# Wiring.net
KiCad netlist of a schematic drawn in EAGLE
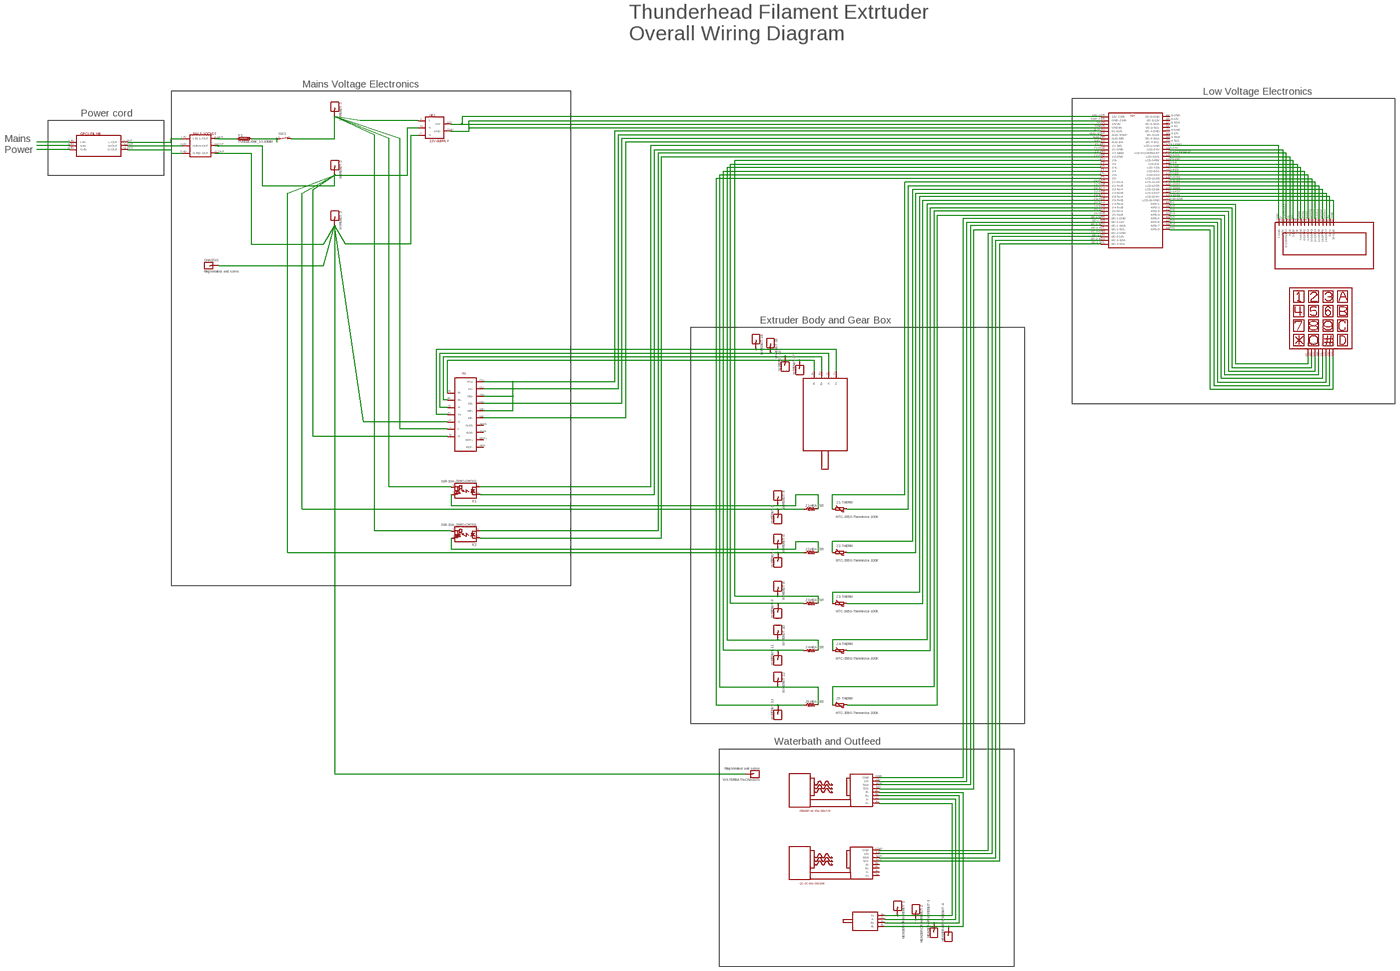
[diagram p0: schematic, sheet 1, overview]
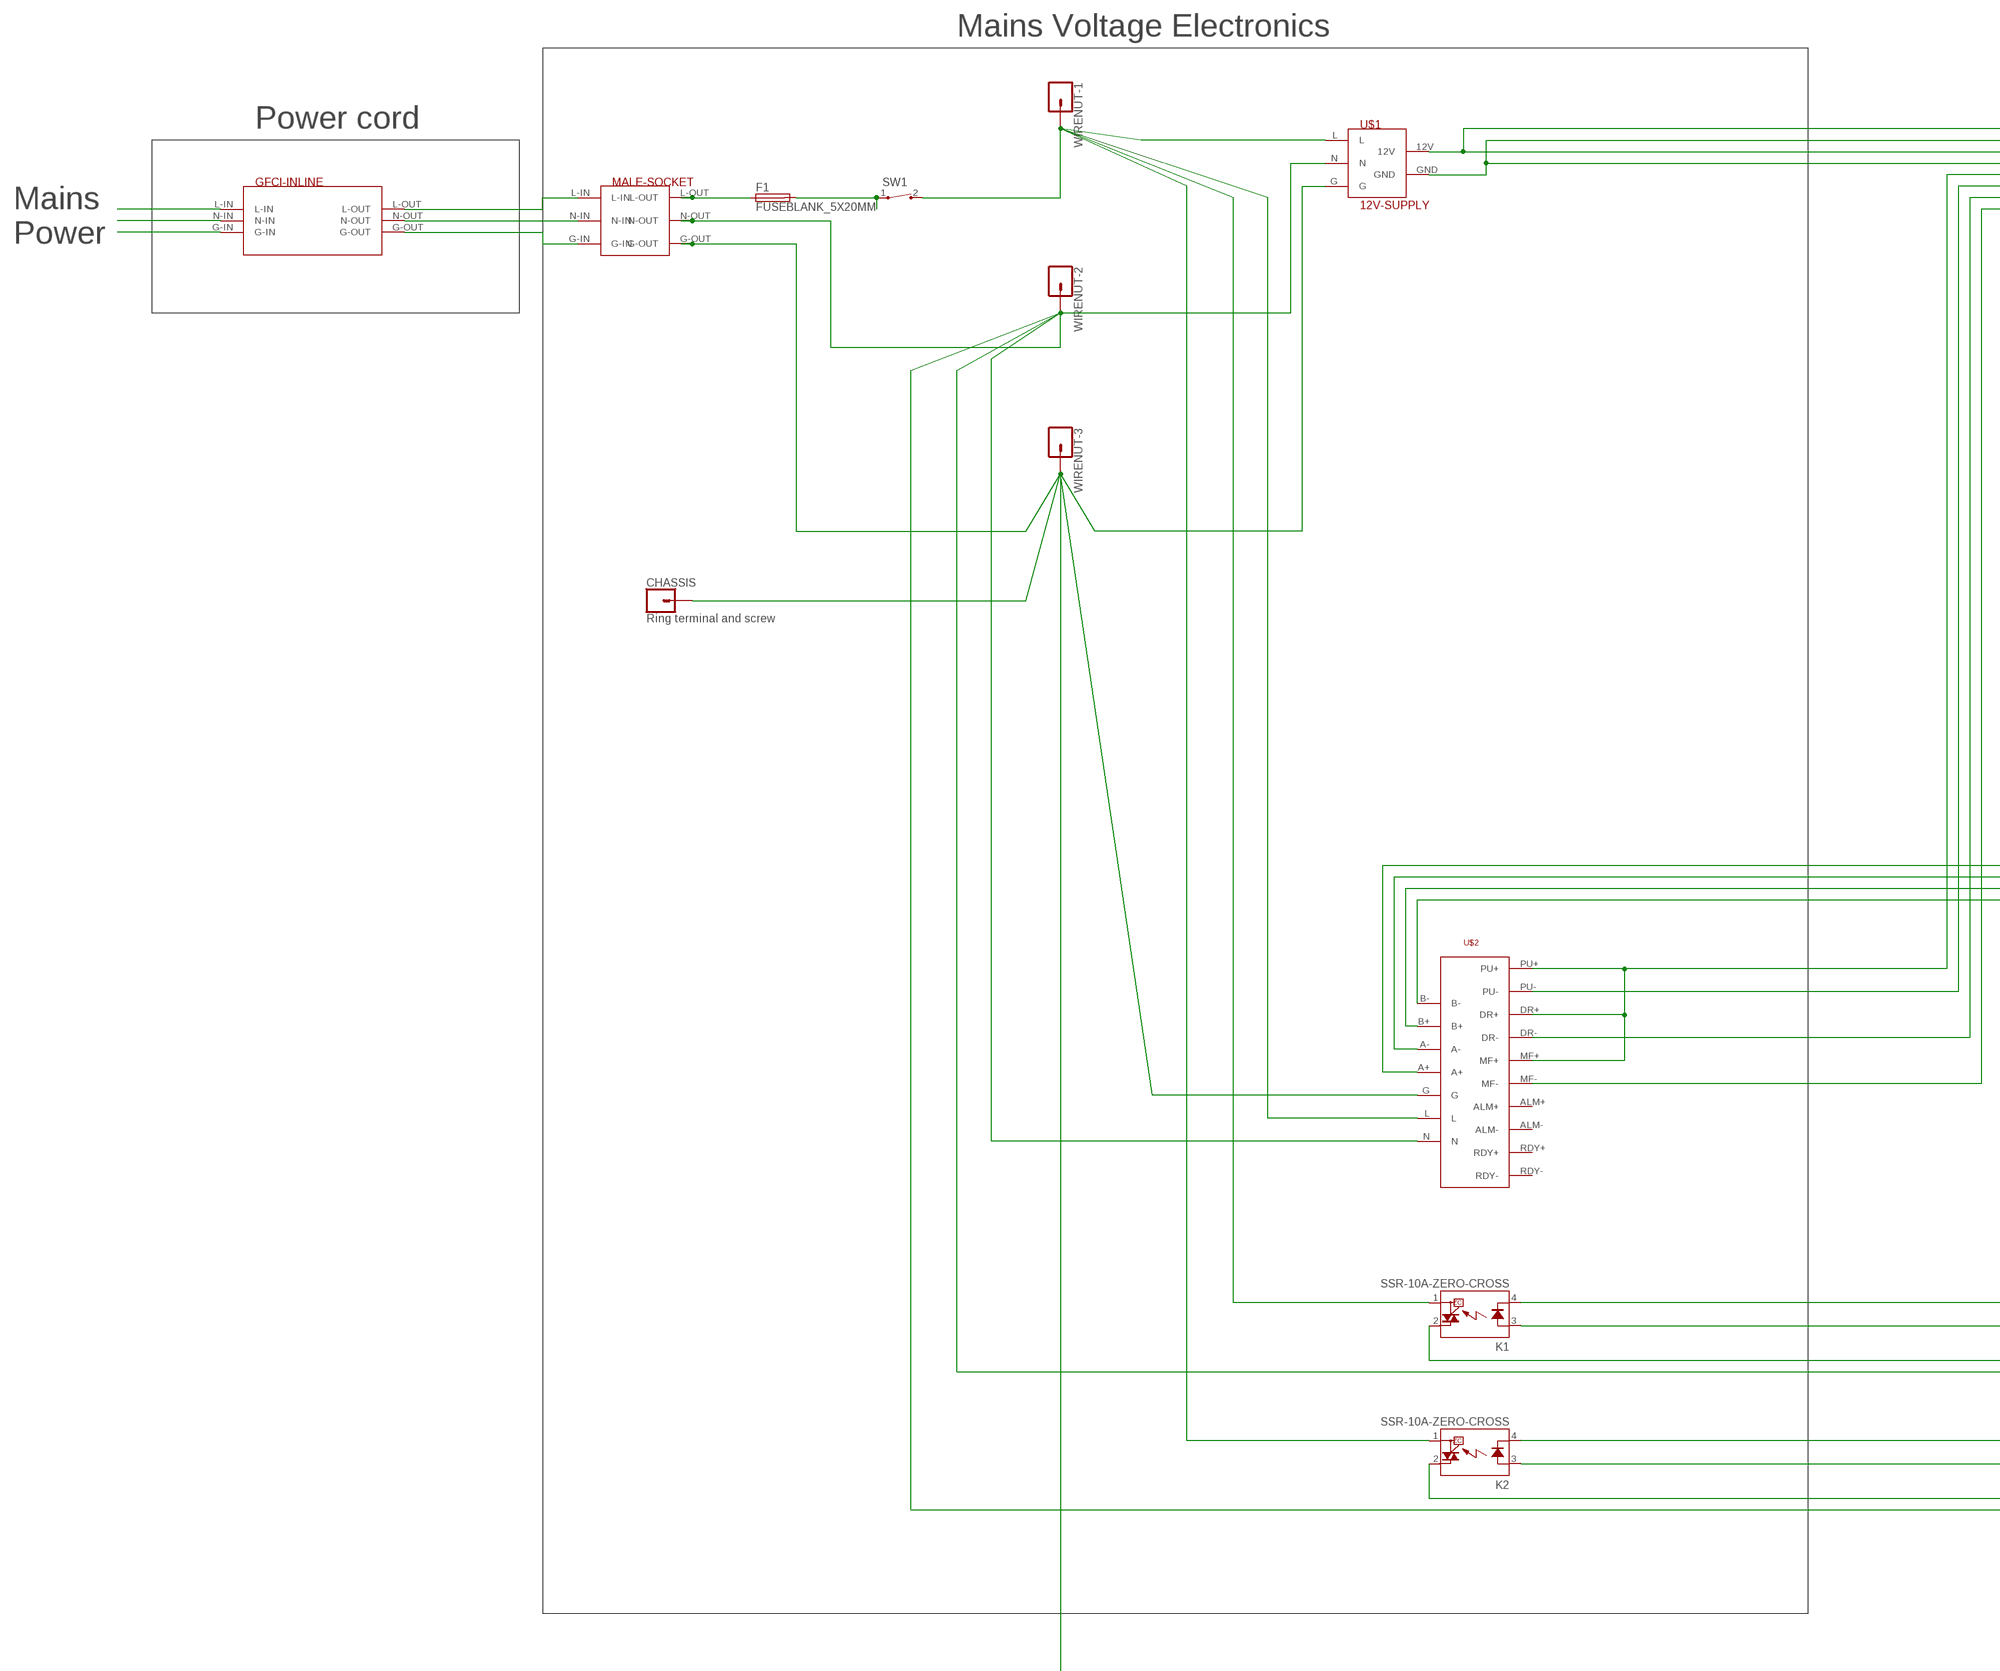
[diagram p1: schematic, sheet 1, part 1 of 4]
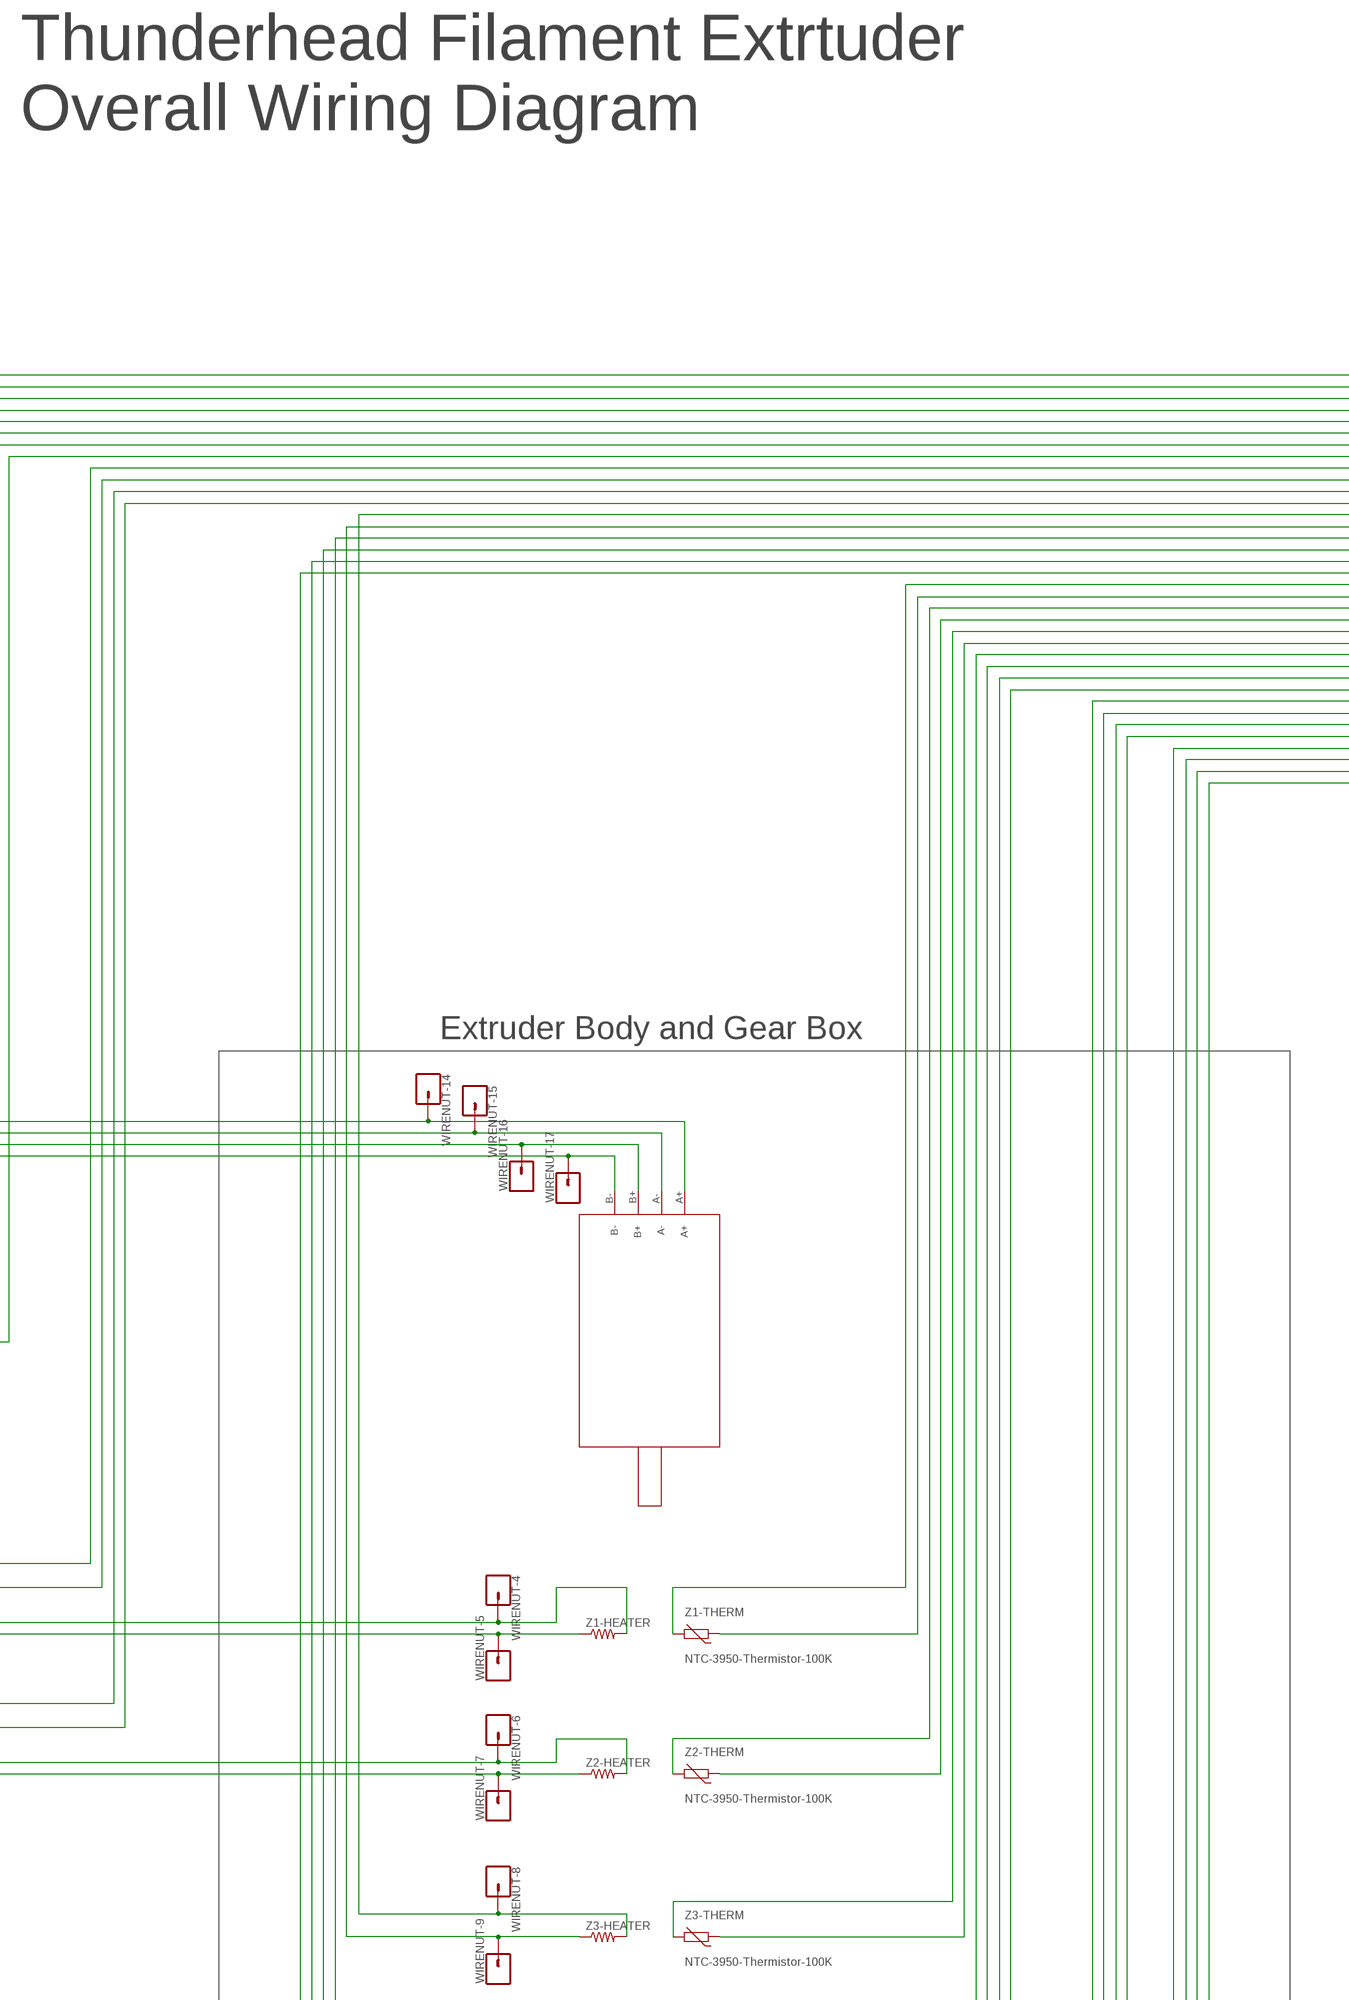
[diagram p2: schematic, sheet 1, part 2 of 4]
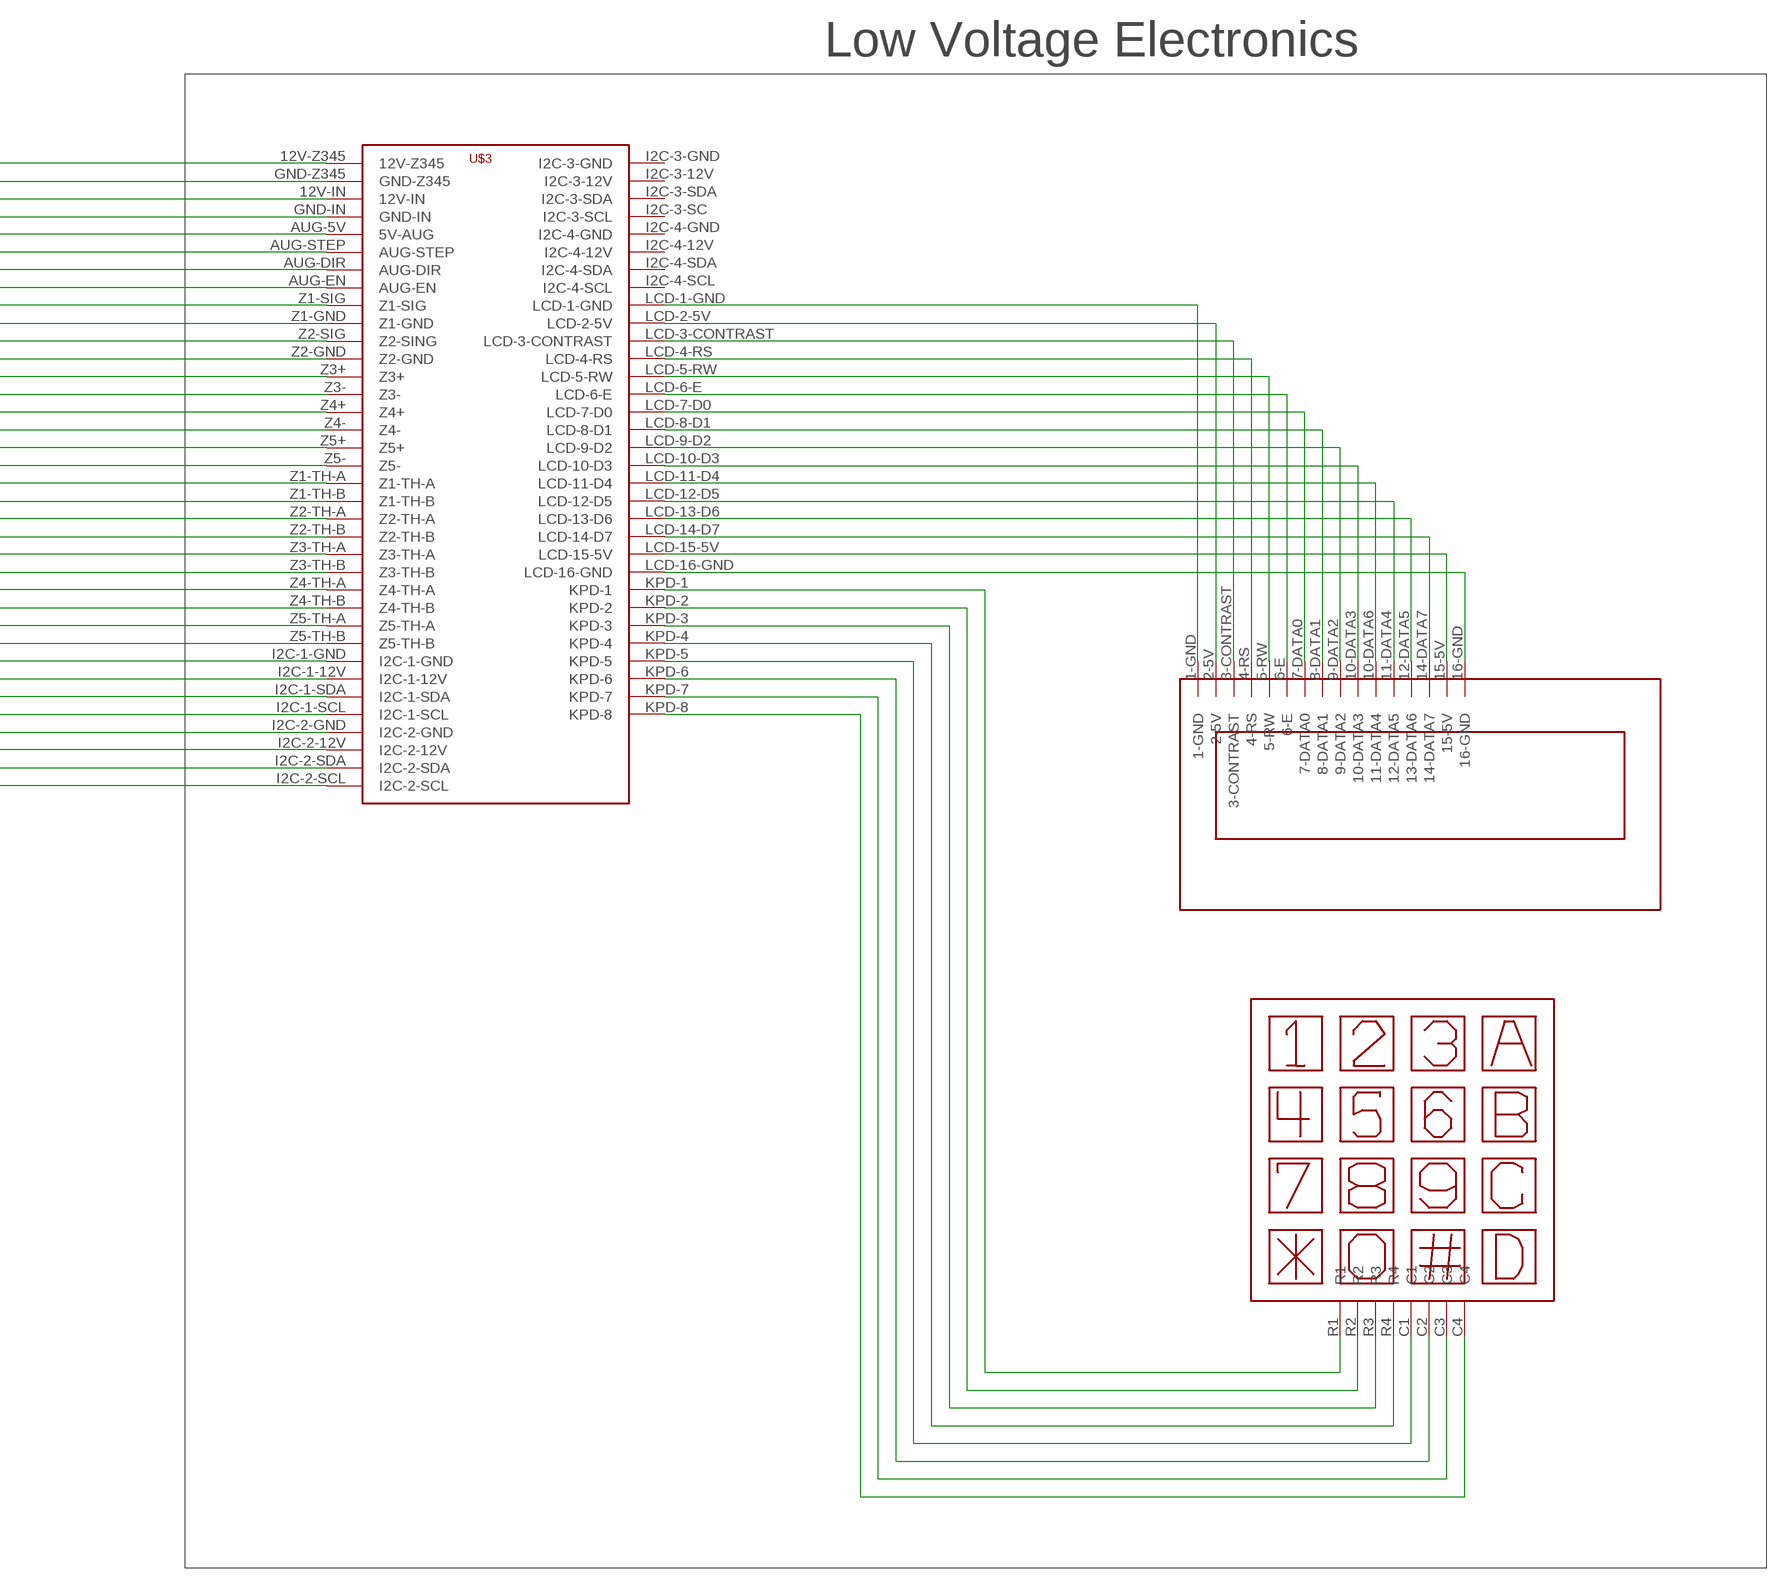
[diagram p3: schematic, sheet 1, part 3 of 4]
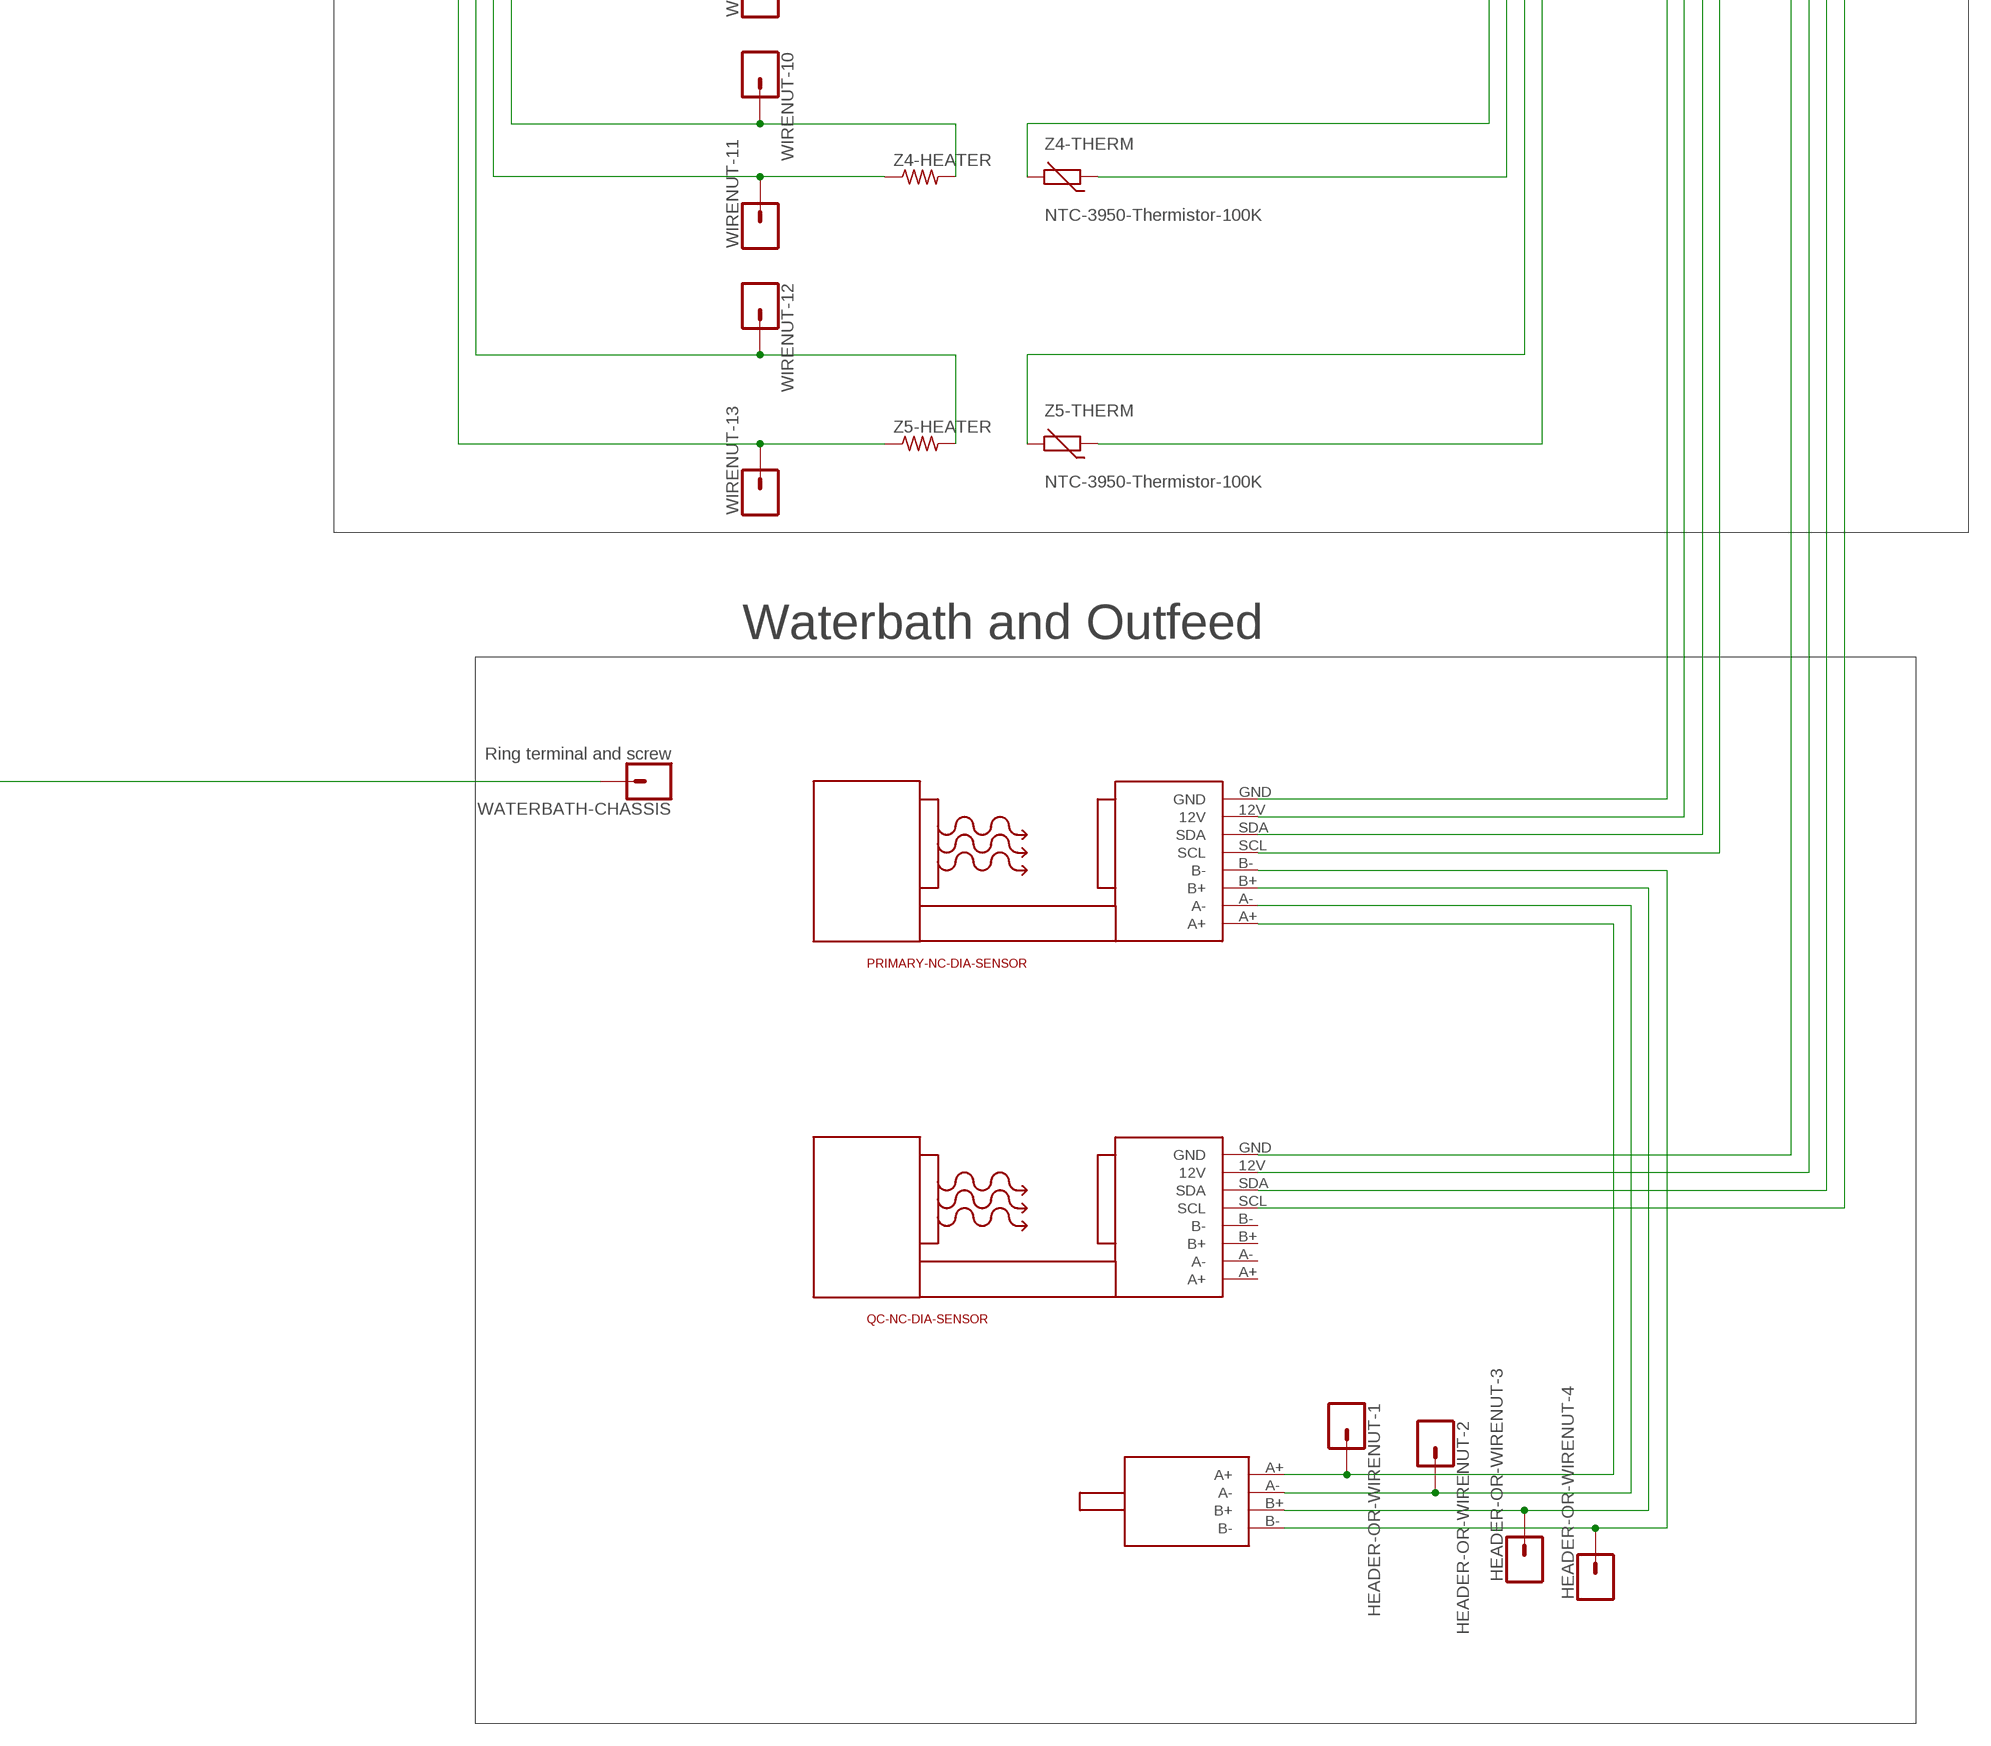
[diagram p4: schematic, sheet 1, part 4 of 4]

(export (version "E")
  (design (tool "Eeschema 10.0.6"))
  (components
    (comp (ref "CHASSIS")
      (value "Ring terminal and screw")
      (footprint "eagle-import:1X01")
      (libsource (lib "eagle-import") (part "CONN_01"))
    )
    (comp (ref "F1")
      (value "FUSEBLANK_5X20MM")
      (footprint "eagle-import:FUSE_HOLDER_5X20MM")
      (libsource (lib "eagle-import") (part "FUSEBLANK_5X20MM"))
    )
    (comp (ref "GFCI-INLINE")
      (value "GFCI-INLINE")
      (footprint "eagle-import:GFCI-INLINE")
      (libsource (lib "eagle-import") (part "GFCI-INLINE"))
    )
    (comp (ref "HEADER-OR-WIRENUT-1")
      (value "CONN_01")
      (footprint "eagle-import:1X01")
      (libsource (lib "eagle-import") (part "CONN_01"))
    )
    (comp (ref "HEADER-OR-WIRENUT-2")
      (value "CONN_01")
      (footprint "eagle-import:1X01")
      (libsource (lib "eagle-import") (part "CONN_01"))
    )
    (comp (ref "HEADER-OR-WIRENUT-3")
      (value "CONN_01")
      (footprint "eagle-import:1X01")
      (libsource (lib "eagle-import") (part "CONN_01"))
    )
    (comp (ref "HEADER-OR-WIRENUT-4")
      (value "CONN_01")
      (footprint "eagle-import:1X01")
      (libsource (lib "eagle-import") (part "CONN_01"))
    )
    (comp (ref "K1")
      (value "SSR-10A-ZERO-CROSS")
      (footprint "eagle-import:SSR-10A-ZERO-CROSS")
      (libsource (lib "eagle-import") (part "SSR-10A-ZERO-CROSS"))
    )
    (comp (ref "K2")
      (value "SSR-10A-ZERO-CROSS")
      (footprint "eagle-import:SSR-10A-ZERO-CROSS")
      (libsource (lib "eagle-import") (part "SSR-10A-ZERO-CROSS"))
    )
    (comp (ref "MALE-SOCKET")
      (value "MALE-SOCKET")
      (footprint "eagle-import:MALE-SOCKET")
      (libsource (lib "eagle-import") (part "MALE-SOCKET"))
    )
    (comp (ref "PRIMARY-NC-DIA-SENSOR")
      (value "NON-CONTACT-DIA-SENSOR")
      (footprint "eagle-import:NON-CONTACT-DIA-SENSOR")
      (libsource (lib "eagle-import") (part "NON-CONTACT-DIA-SENSOR"))
    )
    (comp (ref "QC-NC-DIA-SENSOR")
      (value "NON-CONTACT-DIA-SENSOR")
      (footprint "eagle-import:NON-CONTACT-DIA-SENSOR")
      (libsource (lib "eagle-import") (part "NON-CONTACT-DIA-SENSOR"))
    )
    (comp (ref "SW1")
      (value "CT10-XXXX-A2")
      (footprint "eagle-import:CT10-XXXX-A2")
      (libsource (lib "eagle-import") (part "CT10-XXXX-A2"))
    )
    (comp (ref "U$1")
      (value "12V-SUPPLY")
      (footprint "eagle-import:12V-SUPPLY")
      (libsource (lib "eagle-import") (part "12V-SUPPLY"))
    )
    (comp (ref "U$2")
      (value "DM2722A")
      (footprint "eagle-import:DM2722A")
      (libsource (lib "eagle-import") (part "DM2722A"))
    )
    (comp (ref "U$3")
      (value "THUNDERBOARD")
      (footprint "eagle-import:THUNDERBOARD")
      (libsource (lib "eagle-import") (part "THUNDERBOARD"))
    )
    (comp (ref "U$5")
      (value "STEPPER-MOTOR-NEMA42")
      (footprint "eagle-import:STEPPER-MOTOR-NEMA42")
      (libsource (lib "eagle-import") (part "STEPPER-MOTOR-NEMA42"))
    )
    (comp (ref "U$6")
      (value "STEPPER-MOTOR-NEMA17")
      (footprint "eagle-import:STEPPER-MOTOR-NEMA17")
      (libsource (lib "eagle-import") (part "STEPPER-MOTOR-NEMA17"))
    )
    (comp (ref "U$7")
      (value "LCD-2004")
      (footprint "eagle-import:LCD-2004")
      (libsource (lib "eagle-import") (part "LCD-2004"))
    )
    (comp (ref "U$8")
      (value "KEYPAD")
      (footprint "eagle-import:KEYPAD")
      (libsource (lib "eagle-import") (part "KEYPAD"))
    )
    (comp (ref "WATERBATH-CHASSIS")
      (value "Ring terminal and screw")
      (footprint "eagle-import:1X01")
      (libsource (lib "eagle-import") (part "CONN_01"))
    )
    (comp (ref "WIRENUT-1")
      (value "CONN_01")
      (footprint "eagle-import:1X01")
      (libsource (lib "eagle-import") (part "CONN_01"))
    )
    (comp (ref "WIRENUT-2")
      (value "CONN_01")
      (footprint "eagle-import:1X01")
      (libsource (lib "eagle-import") (part "CONN_01"))
    )
    (comp (ref "WIRENUT-3")
      (value "CONN_01")
      (footprint "eagle-import:1X01")
      (libsource (lib "eagle-import") (part "CONN_01"))
    )
    (comp (ref "WIRENUT-4")
      (value "CONN_01")
      (footprint "eagle-import:1X01")
      (libsource (lib "eagle-import") (part "CONN_01"))
    )
    (comp (ref "WIRENUT-5")
      (value "CONN_01")
      (footprint "eagle-import:1X01")
      (libsource (lib "eagle-import") (part "CONN_01"))
    )
    (comp (ref "WIRENUT-6")
      (value "CONN_01")
      (footprint "eagle-import:1X01")
      (libsource (lib "eagle-import") (part "CONN_01"))
    )
    (comp (ref "WIRENUT-7")
      (value "CONN_01")
      (footprint "eagle-import:1X01")
      (libsource (lib "eagle-import") (part "CONN_01"))
    )
    (comp (ref "WIRENUT-8")
      (value "CONN_01")
      (footprint "eagle-import:1X01")
      (libsource (lib "eagle-import") (part "CONN_01"))
    )
    (comp (ref "WIRENUT-9")
      (value "CONN_01")
      (footprint "eagle-import:1X01")
      (libsource (lib "eagle-import") (part "CONN_01"))
    )
    (comp (ref "WIRENUT-10")
      (value "CONN_01")
      (footprint "eagle-import:1X01")
      (libsource (lib "eagle-import") (part "CONN_01"))
    )
    (comp (ref "WIRENUT-11")
      (value "CONN_01")
      (footprint "eagle-import:1X01")
      (libsource (lib "eagle-import") (part "CONN_01"))
    )
    (comp (ref "WIRENUT-12")
      (value "CONN_01")
      (footprint "eagle-import:1X01")
      (libsource (lib "eagle-import") (part "CONN_01"))
    )
    (comp (ref "WIRENUT-13")
      (value "CONN_01")
      (footprint "eagle-import:1X01")
      (libsource (lib "eagle-import") (part "CONN_01"))
    )
    (comp (ref "WIRENUT-14")
      (value "CONN_01")
      (footprint "eagle-import:1X01")
      (libsource (lib "eagle-import") (part "CONN_01"))
    )
    (comp (ref "WIRENUT-15")
      (value "CONN_01")
      (footprint "eagle-import:1X01")
      (libsource (lib "eagle-import") (part "CONN_01"))
    )
    (comp (ref "WIRENUT-16")
      (value "CONN_01")
      (footprint "eagle-import:1X01")
      (libsource (lib "eagle-import") (part "CONN_01"))
    )
    (comp (ref "WIRENUT-17")
      (value "CONN_01")
      (footprint "eagle-import:1X01")
      (libsource (lib "eagle-import") (part "CONN_01"))
    )
    (comp (ref "Z1-HEATER")
      (value "R-US_0204/2V")
      (footprint "eagle-import:0204V")
      (libsource (lib "eagle-import") (part "R-US_0204/2V"))
    )
    (comp (ref "Z1-THERM")
      (value "NTC-3950-Thermistor-100K")
      (footprint "eagle-import:RS-2,5")
      (libsource (lib "eagle-import") (part "THERMISTOR-2,5"))
    )
    (comp (ref "Z2-HEATER")
      (value "R-US_0204/2V")
      (footprint "eagle-import:0204V")
      (libsource (lib "eagle-import") (part "R-US_0204/2V"))
    )
    (comp (ref "Z2-THERM")
      (value "NTC-3950-Thermistor-100K")
      (footprint "eagle-import:RS-2,5")
      (libsource (lib "eagle-import") (part "THERMISTOR-2,5"))
    )
    (comp (ref "Z3-HEATER")
      (value "R-US_0204/2V")
      (footprint "eagle-import:0204V")
      (libsource (lib "eagle-import") (part "R-US_0204/2V"))
    )
    (comp (ref "Z3-THERM")
      (value "NTC-3950-Thermistor-100K")
      (footprint "eagle-import:RS-2,5")
      (libsource (lib "eagle-import") (part "THERMISTOR-2,5"))
    )
    (comp (ref "Z4-HEATER")
      (value "R-US_0204/2V")
      (footprint "eagle-import:0204V")
      (libsource (lib "eagle-import") (part "R-US_0204/2V"))
    )
    (comp (ref "Z4-THERM")
      (value "NTC-3950-Thermistor-100K")
      (footprint "eagle-import:RS-2,5")
      (libsource (lib "eagle-import") (part "THERMISTOR-2,5"))
    )
    (comp (ref "Z5-HEATER")
      (value "R-US_0204/2V")
      (footprint "eagle-import:0204V")
      (libsource (lib "eagle-import") (part "R-US_0204/2V"))
    )
    (comp (ref "Z5-THERM")
      (value "NTC-3950-Thermistor-100K")
      (footprint "eagle-import:RS-2,5")
      (libsource (lib "eagle-import") (part "THERMISTOR-2,5"))
    )
  )
  (nets
    (net (code "1") (name "Net-(CHASSIS-Pad1)") (class "Default")
      (node (ref "CHASSIS") (pin "1") (pinfunction "1_1") (pintype "passive"))
      (node (ref "MALE-SOCKET") (pin "G-OUT") (pinfunction "G-OUT_G-OUT") (pintype "bidirectional"))
      (node (ref "U$1") (pin "G") (pinfunction "G_G") (pintype "bidirectional"))
      (node (ref "U$2") (pin "G") (pinfunction "G_G") (pintype "bidirectional"))
      (node (ref "WATERBATH-CHASSIS") (pin "1") (pinfunction "1_1") (pintype "passive"))
      (node (ref "WIRENUT-3") (pin "1") (pinfunction "1_1") (pintype "passive"))
    )
    (net (code "2") (name "Net-(F1-Pad1)") (class "Default")
      (node (ref "F1") (pin "1") (pinfunction "1_1") (pintype "passive"))
      (node (ref "MALE-SOCKET") (pin "L-OUT") (pinfunction "L-OUT_L-OUT") (pintype "bidirectional"))
    )
    (net (code "3") (name "Net-(F1-Pad2)") (class "Default")
      (node (ref "F1") (pin "2") (pinfunction "2_2") (pintype "passive"))
      (node (ref "SW1") (pin "1") (pinfunction "1_1") (pintype "passive"))
    )
    (net (code "4") (name "Net-(GFCI-INLINE-PadG-OUT)") (class "Default")
      (node (ref "GFCI-INLINE") (pin "G-OUT") (pinfunction "G-OUT_G-OUT") (pintype "bidirectional"))
      (node (ref "MALE-SOCKET") (pin "G-IN") (pinfunction "G-IN_G-IN") (pintype "bidirectional"))
    )
    (net (code "5") (name "Net-(GFCI-INLINE-PadL-OUT)") (class "Default")
      (node (ref "GFCI-INLINE") (pin "L-OUT") (pinfunction "L-OUT_L-OUT") (pintype "bidirectional"))
      (node (ref "MALE-SOCKET") (pin "L-IN") (pinfunction "L-IN_L-IN") (pintype "bidirectional"))
    )
    (net (code "6") (name "Net-(GFCI-INLINE-PadN-OUT)") (class "Default")
      (node (ref "GFCI-INLINE") (pin "N-OUT") (pinfunction "N-OUT_N-OUT") (pintype "bidirectional"))
      (node (ref "MALE-SOCKET") (pin "N-IN") (pinfunction "N-IN_N-IN") (pintype "bidirectional"))
    )
    (net (code "7") (name "Net-(HEADER-OR-WIRENUT-1-Pad1)") (class "Default")
      (node (ref "HEADER-OR-WIRENUT-1") (pin "1") (pinfunction "1_1") (pintype "passive"))
      (node (ref "PRIMARY-NC-DIA-SENSOR") (pin "A+") (pinfunction "A+_A+") (pintype "bidirectional"))
      (node (ref "U$6") (pin "A+") (pinfunction "A+_A+") (pintype "bidirectional"))
    )
    (net (code "8") (name "Net-(HEADER-OR-WIRENUT-2-Pad1)") (class "Default")
      (node (ref "HEADER-OR-WIRENUT-2") (pin "1") (pinfunction "1_1") (pintype "passive"))
      (node (ref "PRIMARY-NC-DIA-SENSOR") (pin "A-") (pinfunction "A-_A-") (pintype "bidirectional"))
      (node (ref "U$6") (pin "A-") (pinfunction "A-_A-") (pintype "bidirectional"))
    )
    (net (code "9") (name "Net-(HEADER-OR-WIRENUT-3-Pad1)") (class "Default")
      (node (ref "HEADER-OR-WIRENUT-3") (pin "1") (pinfunction "1_1") (pintype "passive"))
      (node (ref "PRIMARY-NC-DIA-SENSOR") (pin "B+") (pinfunction "B+_B+") (pintype "bidirectional"))
      (node (ref "U$6") (pin "B+") (pinfunction "B+_B+") (pintype "bidirectional"))
    )
    (net (code "10") (name "Net-(HEADER-OR-WIRENUT-4-Pad1)") (class "Default")
      (node (ref "HEADER-OR-WIRENUT-4") (pin "1") (pinfunction "1_1") (pintype "passive"))
      (node (ref "PRIMARY-NC-DIA-SENSOR") (pin "B-") (pinfunction "B-_B-") (pintype "bidirectional"))
      (node (ref "U$6") (pin "B-") (pinfunction "B-_B-") (pintype "bidirectional"))
    )
    (net (code "11") (name "Net-(K1-Pad1)") (class "Default")
      (node (ref "K1") (pin "1") (pinfunction "1_1") (pintype "passive"))
      (node (ref "K2") (pin "1") (pinfunction "1_1") (pintype "passive"))
      (node (ref "SW1") (pin "2") (pinfunction "2_2") (pintype "passive"))
      (node (ref "U$1") (pin "L") (pinfunction "L_L") (pintype "bidirectional"))
      (node (ref "U$2") (pin "L") (pinfunction "L_L") (pintype "bidirectional"))
      (node (ref "WIRENUT-1") (pin "1") (pinfunction "1_1") (pintype "passive"))
    )
    (net (code "12") (name "Net-(K1-Pad2)") (class "Default")
      (node (ref "K1") (pin "2") (pinfunction "2_2") (pintype "passive"))
      (node (ref "WIRENUT-4") (pin "1") (pinfunction "1_1") (pintype "passive"))
      (node (ref "Z1-HEATER") (pin "2") (pinfunction "2_2") (pintype "passive"))
    )
    (net (code "13") (name "Net-(K1-Pad3)") (class "Default")
      (node (ref "K1") (pin "3") (pinfunction "3_3") (pintype "passive"))
      (node (ref "U$3") (pin "Z1-GND") (pinfunction "Z1-GND_Z1-GND") (pintype "bidirectional"))
    )
    (net (code "14") (name "Net-(K1-Pad4)") (class "Default")
      (node (ref "K1") (pin "4") (pinfunction "4_4") (pintype "passive"))
      (node (ref "U$3") (pin "Z1-SIG") (pinfunction "Z1-SIG_Z1-SIG") (pintype "bidirectional"))
    )
    (net (code "15") (name "Net-(K2-Pad2)") (class "Default")
      (node (ref "K2") (pin "2") (pinfunction "2_2") (pintype "passive"))
      (node (ref "WIRENUT-6") (pin "1") (pinfunction "1_1") (pintype "passive"))
      (node (ref "Z2-HEATER") (pin "2") (pinfunction "2_2") (pintype "passive"))
    )
    (net (code "16") (name "Net-(K2-Pad3)") (class "Default")
      (node (ref "K2") (pin "3") (pinfunction "3_3") (pintype "passive"))
      (node (ref "U$3") (pin "Z2-GND") (pinfunction "Z2-GND_Z2-GND") (pintype "bidirectional"))
    )
    (net (code "17") (name "Net-(MALE-SOCKET-PadN-OUT)") (class "Default")
      (node (ref "MALE-SOCKET") (pin "N-OUT") (pinfunction "N-OUT_N-OUT") (pintype "bidirectional"))
      (node (ref "U$1") (pin "N") (pinfunction "N_N") (pintype "bidirectional"))
      (node (ref "U$2") (pin "N") (pinfunction "N_N") (pintype "bidirectional"))
      (node (ref "WIRENUT-2") (pin "1") (pinfunction "1_1") (pintype "passive"))
      (node (ref "WIRENUT-5") (pin "1") (pinfunction "1_1") (pintype "passive"))
      (node (ref "WIRENUT-7") (pin "1") (pinfunction "1_1") (pintype "passive"))
      (node (ref "Z1-HEATER") (pin "1") (pinfunction "1_1") (pintype "passive"))
      (node (ref "Z2-HEATER") (pin "1") (pinfunction "1_1") (pintype "passive"))
    )
    (net (code "18") (name "Net-(PRIMARY-NC-DIA-SENSOR-Pad12V)") (class "Default")
      (node (ref "PRIMARY-NC-DIA-SENSOR") (pin "12V") (pinfunction "12V_12V") (pintype "bidirectional"))
      (node (ref "U$3") (pin "I2C-1-12V") (pinfunction "I2C-1-12V_I2C-1-12V") (pintype "bidirectional"))
    )
    (net (code "19") (name "Net-(PRIMARY-NC-DIA-SENSOR-PadGND)") (class "Default")
      (node (ref "PRIMARY-NC-DIA-SENSOR") (pin "GND") (pinfunction "GND_GND") (pintype "bidirectional"))
      (node (ref "U$3") (pin "I2C-1-GND") (pinfunction "I2C-1-GND_I2C-1-GND") (pintype "bidirectional"))
    )
    (net (code "20") (name "Net-(PRIMARY-NC-DIA-SENSOR-PadSCL)") (class "Default")
      (node (ref "PRIMARY-NC-DIA-SENSOR") (pin "SCL") (pinfunction "SCL_SCL") (pintype "bidirectional"))
      (node (ref "U$3") (pin "I2C-1-SCL") (pinfunction "I2C-1-SCL_I2C-1-SCL") (pintype "bidirectional"))
    )
    (net (code "21") (name "Net-(PRIMARY-NC-DIA-SENSOR-PadSDA)") (class "Default")
      (node (ref "PRIMARY-NC-DIA-SENSOR") (pin "SDA") (pinfunction "SDA_SDA") (pintype "bidirectional"))
      (node (ref "U$3") (pin "I2C-1-SDA") (pinfunction "I2C-1-SDA_I2C-1-SDA") (pintype "bidirectional"))
    )
    (net (code "22") (name "Net-(QC-NC-DIA-SENSOR-Pad12V)") (class "Default")
      (node (ref "QC-NC-DIA-SENSOR") (pin "12V") (pinfunction "12V_12V") (pintype "bidirectional"))
      (node (ref "U$3") (pin "I2C-2-12V") (pinfunction "I2C-2-12V_I2C-2-12V") (pintype "bidirectional"))
    )
    (net (code "23") (name "Net-(QC-NC-DIA-SENSOR-PadGND)") (class "Default")
      (node (ref "QC-NC-DIA-SENSOR") (pin "GND") (pinfunction "GND_GND") (pintype "bidirectional"))
      (node (ref "U$3") (pin "I2C-2-GND") (pinfunction "I2C-2-GND_I2C-2-GND") (pintype "bidirectional"))
    )
    (net (code "24") (name "Net-(QC-NC-DIA-SENSOR-PadSCL)") (class "Default")
      (node (ref "QC-NC-DIA-SENSOR") (pin "SCL") (pinfunction "SCL_SCL") (pintype "bidirectional"))
      (node (ref "U$3") (pin "I2C-2-SCL") (pinfunction "I2C-2-SCL_I2C-2-SCL") (pintype "bidirectional"))
    )
    (net (code "25") (name "Net-(QC-NC-DIA-SENSOR-PadSDA)") (class "Default")
      (node (ref "QC-NC-DIA-SENSOR") (pin "SDA") (pinfunction "SDA_SDA") (pintype "bidirectional"))
      (node (ref "U$3") (pin "I2C-2-SDA") (pinfunction "I2C-2-SDA_I2C-2-SDA") (pintype "bidirectional"))
    )
    (net (code "26") (name "Net-(U$1-Pad12V)") (class "Default")
      (node (ref "U$1") (pin "12V") (pinfunction "12V_12V") (pintype "bidirectional"))
      (node (ref "U$3") (pin "12V-IN") (pinfunction "12V-IN_12V-IN") (pintype "bidirectional"))
      (node (ref "U$3") (pin "12V-Z345") (pinfunction "12V-Z345_12V-Z345") (pintype "bidirectional"))
    )
    (net (code "27") (name "Net-(U$1-PadGND)") (class "Default")
      (node (ref "U$1") (pin "GND") (pinfunction "GND_GND") (pintype "bidirectional"))
      (node (ref "U$3") (pin "GND-IN") (pinfunction "GND-IN_GND-IN") (pintype "bidirectional"))
      (node (ref "U$3") (pin "GND-Z345") (pinfunction "GND-Z345_GND-Z345") (pintype "bidirectional"))
    )
    (net (code "28") (name "Net-(U$2-PadA+)") (class "Default")
      (node (ref "U$2") (pin "A+") (pinfunction "A+_A+") (pintype "bidirectional"))
      (node (ref "U$5") (pin "A+") (pinfunction "A+_A+") (pintype "bidirectional"))
      (node (ref "WIRENUT-14") (pin "1") (pinfunction "1_1") (pintype "passive"))
    )
    (net (code "29") (name "Net-(U$2-PadA-)") (class "Default")
      (node (ref "U$2") (pin "A-") (pinfunction "A-_A-") (pintype "bidirectional"))
      (node (ref "U$5") (pin "A-") (pinfunction "A-_A-") (pintype "bidirectional"))
      (node (ref "WIRENUT-15") (pin "1") (pinfunction "1_1") (pintype "passive"))
    )
    (net (code "30") (name "Net-(U$2-PadB+)") (class "Default")
      (node (ref "U$2") (pin "B+") (pinfunction "B+_B+") (pintype "bidirectional"))
      (node (ref "U$5") (pin "B+") (pinfunction "B+_B+") (pintype "bidirectional"))
      (node (ref "WIRENUT-16") (pin "1") (pinfunction "1_1") (pintype "passive"))
    )
    (net (code "31") (name "Net-(U$2-PadB-)") (class "Default")
      (node (ref "U$2") (pin "B-") (pinfunction "B-_B-") (pintype "bidirectional"))
      (node (ref "U$5") (pin "B-") (pinfunction "B-_B-") (pintype "bidirectional"))
      (node (ref "WIRENUT-17") (pin "1") (pinfunction "1_1") (pintype "passive"))
    )
    (net (code "32") (name "Net-(U$2-PadDR-)") (class "Default")
      (node (ref "U$2") (pin "DR-") (pinfunction "DR-_DR-") (pintype "bidirectional"))
      (node (ref "U$3") (pin "AUG-DIR") (pinfunction "AUG-DIR_AUG-DIR") (pintype "bidirectional"))
    )
    (net (code "33") (name "Net-(U$2-PadMF-)") (class "Default")
      (node (ref "U$2") (pin "MF-") (pinfunction "MF-_MF-") (pintype "bidirectional"))
      (node (ref "U$3") (pin "AUG-EN") (pinfunction "AUG-EN_AUG-EN") (pintype "bidirectional"))
    )
    (net (code "34") (name "Net-(U$2-PadPU-)") (class "Default")
      (node (ref "U$2") (pin "PU-") (pinfunction "PU-_PU-") (pintype "bidirectional"))
      (node (ref "U$3") (pin "AUG-STEP") (pinfunction "AUG-STEP_AUG-STEP") (pintype "bidirectional"))
    )
    (net (code "35") (name "Net-(U$3-5V-AUG)") (class "Default")
      (node (ref "U$2") (pin "DR+") (pinfunction "DR+_DR+") (pintype "bidirectional"))
      (node (ref "U$2") (pin "MF+") (pinfunction "MF+_MF+") (pintype "bidirectional"))
      (node (ref "U$2") (pin "PU+") (pinfunction "PU+_PU+") (pintype "bidirectional"))
      (node (ref "U$3") (pin "AUG-5V") (pinfunction "5V-AUG_AUG-5V") (pintype "bidirectional"))
    )
    (net (code "36") (name "Net-(U$3-PadKPD-1)") (class "Default")
      (node (ref "U$3") (pin "KPD-1") (pinfunction "KPD-1_KPD-1") (pintype "bidirectional"))
      (node (ref "U$8") (pin "R1") (pinfunction "R1_R1") (pintype "bidirectional"))
    )
    (net (code "37") (name "Net-(U$3-PadKPD-2)") (class "Default")
      (node (ref "U$3") (pin "KPD-2") (pinfunction "KPD-2_KPD-2") (pintype "bidirectional"))
      (node (ref "U$8") (pin "R2") (pinfunction "R2_R2") (pintype "bidirectional"))
    )
    (net (code "38") (name "Net-(U$3-PadKPD-3)") (class "Default")
      (node (ref "U$3") (pin "KPD-3") (pinfunction "KPD-3_KPD-3") (pintype "bidirectional"))
      (node (ref "U$8") (pin "R3") (pinfunction "R3_R3") (pintype "bidirectional"))
    )
    (net (code "39") (name "Net-(U$3-PadKPD-4)") (class "Default")
      (node (ref "U$3") (pin "KPD-4") (pinfunction "KPD-4_KPD-4") (pintype "bidirectional"))
      (node (ref "U$8") (pin "R4") (pinfunction "R4_R4") (pintype "bidirectional"))
    )
    (net (code "40") (name "Net-(U$3-PadKPD-5)") (class "Default")
      (node (ref "U$3") (pin "KPD-5") (pinfunction "KPD-5_KPD-5") (pintype "bidirectional"))
      (node (ref "U$8") (pin "C1") (pinfunction "C1_C1") (pintype "bidirectional"))
    )
    (net (code "41") (name "Net-(U$3-PadKPD-6)") (class "Default")
      (node (ref "U$3") (pin "KPD-6") (pinfunction "KPD-6_KPD-6") (pintype "bidirectional"))
      (node (ref "U$8") (pin "C2") (pinfunction "C2_C2") (pintype "bidirectional"))
    )
    (net (code "42") (name "Net-(U$3-PadKPD-7)") (class "Default")
      (node (ref "U$3") (pin "KPD-7") (pinfunction "KPD-7_KPD-7") (pintype "bidirectional"))
      (node (ref "U$8") (pin "C3") (pinfunction "C3_C3") (pintype "bidirectional"))
    )
    (net (code "43") (name "Net-(U$3-PadKPD-8)") (class "Default")
      (node (ref "U$3") (pin "KPD-8") (pinfunction "KPD-8_KPD-8") (pintype "bidirectional"))
      (node (ref "U$8") (pin "C4") (pinfunction "C4_C4") (pintype "bidirectional"))
    )
    (net (code "44") (name "Net-(U$3-PadLCD-1-GND)") (class "Default")
      (node (ref "U$3") (pin "LCD-1-GND") (pinfunction "LCD-1-GND_LCD-1-GND") (pintype "bidirectional"))
      (node (ref "U$7") (pin "1-GND") (pinfunction "1-GND_1-GND") (pintype "bidirectional"))
    )
    (net (code "45") (name "Net-(U$3-PadLCD-2-5V)") (class "Default")
      (node (ref "U$3") (pin "LCD-2-5V") (pinfunction "LCD-2-5V_LCD-2-5V") (pintype "bidirectional"))
      (node (ref "U$7") (pin "2-5V") (pinfunction "2-5V_2-5V") (pintype "bidirectional"))
    )
    (net (code "46") (name "Net-(U$3-PadLCD-3-CONTRAST)") (class "Default")
      (node (ref "U$3") (pin "LCD-3-CONTRAST") (pinfunction "LCD-3-CONTRAST_LCD-3-CONTRAST") (pintype "bidirectional"))
      (node (ref "U$7") (pin "3-CONTRAST") (pinfunction "3-CONTRAST_3-CONTRAST") (pintype "bidirectional"))
    )
    (net (code "47") (name "Net-(U$3-PadLCD-4-RS)") (class "Default")
      (node (ref "U$3") (pin "LCD-4-RS") (pinfunction "LCD-4-RS_LCD-4-RS") (pintype "bidirectional"))
      (node (ref "U$7") (pin "4-RS") (pinfunction "4-RS_4-RS") (pintype "bidirectional"))
    )
    (net (code "48") (name "Net-(U$3-PadLCD-5-RW)") (class "Default")
      (node (ref "U$3") (pin "LCD-5-RW") (pinfunction "LCD-5-RW_LCD-5-RW") (pintype "bidirectional"))
      (node (ref "U$7") (pin "5-RW") (pinfunction "5-RW_5-RW") (pintype "bidirectional"))
    )
    (net (code "49") (name "Net-(U$3-PadLCD-6-E)") (class "Default")
      (node (ref "U$3") (pin "LCD-6-E") (pinfunction "LCD-6-E_LCD-6-E") (pintype "bidirectional"))
      (node (ref "U$7") (pin "6-E") (pinfunction "6-E_6-E") (pintype "bidirectional"))
    )
    (net (code "50") (name "Net-(U$3-PadLCD-7-D0)") (class "Default")
      (node (ref "U$3") (pin "LCD-7-D0") (pinfunction "LCD-7-D0_LCD-7-D0") (pintype "bidirectional"))
      (node (ref "U$7") (pin "7-DATA0") (pinfunction "7-DATA0_7-DATA0") (pintype "bidirectional"))
    )
    (net (code "51") (name "Net-(U$3-PadLCD-8-D1)") (class "Default")
      (node (ref "U$3") (pin "LCD-8-D1") (pinfunction "LCD-8-D1_LCD-8-D1") (pintype "bidirectional"))
      (node (ref "U$7") (pin "8-DATA1") (pinfunction "8-DATA1_8-DATA1") (pintype "bidirectional"))
    )
    (net (code "52") (name "Net-(U$3-PadLCD-9-D2)") (class "Default")
      (node (ref "U$3") (pin "LCD-9-D2") (pinfunction "LCD-9-D2_LCD-9-D2") (pintype "bidirectional"))
      (node (ref "U$7") (pin "9-DATA2") (pinfunction "9-DATA2_9-DATA2") (pintype "bidirectional"))
    )
    (net (code "53") (name "Net-(U$3-PadLCD-10-D3)") (class "Default")
      (node (ref "U$3") (pin "LCD-10-D3") (pinfunction "LCD-10-D3_LCD-10-D3") (pintype "bidirectional"))
      (node (ref "U$7") (pin "10-DATA3") (pinfunction "10-DATA3_10-DATA3") (pintype "bidirectional"))
    )
    (net (code "54") (name "Net-(U$3-PadLCD-14-D7)") (class "Default")
      (node (ref "U$3") (pin "LCD-14-D7") (pinfunction "LCD-14-D7_LCD-14-D7") (pintype "bidirectional"))
      (node (ref "U$7") (pin "14-DATA7") (pinfunction "14-DATA7_14-DATA7") (pintype "bidirectional"))
    )
    (net (code "55") (name "Net-(U$3-PadLCD-15-5V)") (class "Default")
      (node (ref "U$3") (pin "LCD-15-5V") (pinfunction "LCD-15-5V_LCD-15-5V") (pintype "bidirectional"))
      (node (ref "U$7") (pin "15-5V") (pinfunction "15-5V_15-5V") (pintype "bidirectional"))
    )
    (net (code "56") (name "Net-(U$3-PadLCD-16-GND)") (class "Default")
      (node (ref "U$3") (pin "LCD-16-GND") (pinfunction "LCD-16-GND_LCD-16-GND") (pintype "bidirectional"))
      (node (ref "U$7") (pin "16-GND") (pinfunction "16-GND_16-GND") (pintype "bidirectional"))
    )
    (net (code "57") (name "Net-(U$3-PadZ1-TH-A)") (class "Default")
      (node (ref "U$3") (pin "Z1-TH-A") (pinfunction "Z1-TH-A_Z1-TH-A") (pintype "bidirectional"))
      (node (ref "Z1-THERM") (pin "2") (pinfunction "2_2") (pintype "passive"))
    )
    (net (code "58") (name "Net-(U$3-PadZ1-TH-B)") (class "Default")
      (node (ref "U$3") (pin "Z1-TH-B") (pinfunction "Z1-TH-B_Z1-TH-B") (pintype "bidirectional"))
      (node (ref "Z1-THERM") (pin "1") (pinfunction "1_1") (pintype "passive"))
    )
    (net (code "59") (name "Net-(U$3-PadZ2-TH-A)") (class "Default")
      (node (ref "U$3") (pin "Z2-TH-A") (pinfunction "Z2-TH-A_Z2-TH-A") (pintype "bidirectional"))
      (node (ref "Z2-THERM") (pin "2") (pinfunction "2_2") (pintype "passive"))
    )
    (net (code "60") (name "Net-(U$3-PadZ2-TH-B)") (class "Default")
      (node (ref "U$3") (pin "Z2-TH-B") (pinfunction "Z2-TH-B_Z2-TH-B") (pintype "bidirectional"))
      (node (ref "Z2-THERM") (pin "1") (pinfunction "1_1") (pintype "passive"))
    )
    (net (code "61") (name "Net-(U$3-PadZ3+)") (class "Default")
      (node (ref "U$3") (pin "Z3+") (pinfunction "Z3+_Z3+") (pintype "bidirectional"))
      (node (ref "WIRENUT-8") (pin "1") (pinfunction "1_1") (pintype "passive"))
      (node (ref "Z3-HEATER") (pin "2") (pinfunction "2_2") (pintype "passive"))
    )
    (net (code "62") (name "Net-(U$3-PadZ3-)") (class "Default")
      (node (ref "U$3") (pin "Z3-") (pinfunction "Z3-_Z3-") (pintype "bidirectional"))
      (node (ref "WIRENUT-9") (pin "1") (pinfunction "1_1") (pintype "passive"))
      (node (ref "Z3-HEATER") (pin "1") (pinfunction "1_1") (pintype "passive"))
    )
    (net (code "63") (name "Net-(U$3-PadZ3-TH-A)") (class "Default")
      (node (ref "U$3") (pin "Z3-TH-A") (pinfunction "Z3-TH-A_Z3-TH-A") (pintype "bidirectional"))
      (node (ref "Z3-THERM") (pin "2") (pinfunction "2_2") (pintype "passive"))
    )
    (net (code "64") (name "Net-(U$3-PadZ3-TH-B)") (class "Default")
      (node (ref "U$3") (pin "Z3-TH-B") (pinfunction "Z3-TH-B_Z3-TH-B") (pintype "bidirectional"))
      (node (ref "Z3-THERM") (pin "1") (pinfunction "1_1") (pintype "passive"))
    )
    (net (code "65") (name "Net-(U$3-PadZ4+)") (class "Default")
      (node (ref "U$3") (pin "Z4+") (pinfunction "Z4+_Z4+") (pintype "bidirectional"))
      (node (ref "WIRENUT-10") (pin "1") (pinfunction "1_1") (pintype "passive"))
      (node (ref "Z4-HEATER") (pin "2") (pinfunction "2_2") (pintype "passive"))
    )
    (net (code "66") (name "Net-(U$3-PadZ4-)") (class "Default")
      (node (ref "U$3") (pin "Z4-") (pinfunction "Z4-_Z4-") (pintype "bidirectional"))
      (node (ref "WIRENUT-11") (pin "1") (pinfunction "1_1") (pintype "passive"))
      (node (ref "Z4-HEATER") (pin "1") (pinfunction "1_1") (pintype "passive"))
    )
    (net (code "67") (name "Net-(U$3-PadZ4-TH-A)") (class "Default")
      (node (ref "U$3") (pin "Z4-TH-A") (pinfunction "Z4-TH-A_Z4-TH-A") (pintype "bidirectional"))
      (node (ref "Z4-THERM") (pin "2") (pinfunction "2_2") (pintype "passive"))
    )
    (net (code "68") (name "Net-(U$3-PadZ4-TH-B)") (class "Default")
      (node (ref "U$3") (pin "Z4-TH-B") (pinfunction "Z4-TH-B_Z4-TH-B") (pintype "bidirectional"))
      (node (ref "Z4-THERM") (pin "1") (pinfunction "1_1") (pintype "passive"))
    )
    (net (code "69") (name "Net-(U$3-PadZ5+)") (class "Default")
      (node (ref "U$3") (pin "Z5+") (pinfunction "Z5+_Z5+") (pintype "bidirectional"))
      (node (ref "WIRENUT-12") (pin "1") (pinfunction "1_1") (pintype "passive"))
      (node (ref "Z5-HEATER") (pin "2") (pinfunction "2_2") (pintype "passive"))
    )
    (net (code "70") (name "Net-(U$3-PadZ5-)") (class "Default")
      (node (ref "U$3") (pin "Z5-") (pinfunction "Z5-_Z5-") (pintype "bidirectional"))
      (node (ref "WIRENUT-13") (pin "1") (pinfunction "1_1") (pintype "passive"))
      (node (ref "Z5-HEATER") (pin "1") (pinfunction "1_1") (pintype "passive"))
    )
    (net (code "71") (name "Net-(U$3-PadZ5-TH-A)") (class "Default")
      (node (ref "U$3") (pin "Z5-TH-A") (pinfunction "Z5-TH-A_Z5-TH-A") (pintype "bidirectional"))
      (node (ref "Z5-THERM") (pin "2") (pinfunction "2_2") (pintype "passive"))
    )
    (net (code "72") (name "Net-(U$3-PadZ5-TH-B)") (class "Default")
      (node (ref "U$3") (pin "Z5-TH-B") (pinfunction "Z5-TH-B_Z5-TH-B") (pintype "bidirectional"))
      (node (ref "Z5-THERM") (pin "1") (pinfunction "1_1") (pintype "passive"))
    )
    (net (code "73") (name "Net-(U$3-Z2-SING)") (class "Default")
      (node (ref "K2") (pin "4") (pinfunction "4_4") (pintype "passive"))
      (node (ref "U$3") (pin "Z2-SIG") (pinfunction "Z2-SING_Z2-SIG") (pintype "bidirectional"))
    )
    (net (code "74") (name "Net-(U$7-11-DATA4)") (class "Default")
      (node (ref "U$3") (pin "LCD-11-D4") (pinfunction "LCD-11-D4_LCD-11-D4") (pintype "bidirectional"))
      (node (ref "U$7") (pin "10-DATA6") (pinfunction "11-DATA4_10-DATA6") (pintype "bidirectional"))
    )
    (net (code "75") (name "Net-(U$7-12-DATA5)") (class "Default")
      (node (ref "U$3") (pin "LCD-12-D5") (pinfunction "LCD-12-D5_LCD-12-D5") (pintype "bidirectional"))
      (node (ref "U$7") (pin "11-DATA4") (pinfunction "12-DATA5_11-DATA4") (pintype "bidirectional"))
    )
    (net (code "76") (name "Net-(U$7-13-DATA6)") (class "Default")
      (node (ref "U$3") (pin "LCD-13-D6") (pinfunction "LCD-13-D6_LCD-13-D6") (pintype "bidirectional"))
      (node (ref "U$7") (pin "12-DATA5") (pinfunction "13-DATA6_12-DATA5") (pintype "bidirectional"))
    )
    (net (code "77") (name "unconnected-(GFCI-INLINE-PadG-IN)") (class "Default")
      (node (ref "GFCI-INLINE") (pin "G-IN") (pinfunction "G-IN_G-IN") (pintype "bidirectional"))
    )
    (net (code "78") (name "unconnected-(GFCI-INLINE-PadL-IN)") (class "Default")
      (node (ref "GFCI-INLINE") (pin "L-IN") (pinfunction "L-IN_L-IN") (pintype "bidirectional"))
    )
    (net (code "79") (name "unconnected-(GFCI-INLINE-PadN-IN)") (class "Default")
      (node (ref "GFCI-INLINE") (pin "N-IN") (pinfunction "N-IN_N-IN") (pintype "bidirectional"))
    )
    (net (code "80") (name "unconnected-(QC-NC-DIA-SENSOR-PadA+)") (class "Default")
      (node (ref "QC-NC-DIA-SENSOR") (pin "A+") (pinfunction "A+_A+") (pintype "bidirectional"))
    )
    (net (code "81") (name "unconnected-(QC-NC-DIA-SENSOR-PadA-)") (class "Default")
      (node (ref "QC-NC-DIA-SENSOR") (pin "A-") (pinfunction "A-_A-") (pintype "bidirectional"))
    )
    (net (code "82") (name "unconnected-(QC-NC-DIA-SENSOR-PadB+)") (class "Default")
      (node (ref "QC-NC-DIA-SENSOR") (pin "B+") (pinfunction "B+_B+") (pintype "bidirectional"))
    )
    (net (code "83") (name "unconnected-(QC-NC-DIA-SENSOR-PadB-)") (class "Default")
      (node (ref "QC-NC-DIA-SENSOR") (pin "B-") (pinfunction "B-_B-") (pintype "bidirectional"))
    )
    (net (code "84") (name "unconnected-(U$2-PadALM+)") (class "Default")
      (node (ref "U$2") (pin "ALM+") (pinfunction "ALM+_ALM+") (pintype "bidirectional"))
    )
    (net (code "85") (name "unconnected-(U$2-PadALM-)") (class "Default")
      (node (ref "U$2") (pin "ALM-") (pinfunction "ALM-_ALM-") (pintype "bidirectional"))
    )
    (net (code "86") (name "unconnected-(U$2-PadRDY+)") (class "Default")
      (node (ref "U$2") (pin "RDY+") (pinfunction "RDY+_RDY+") (pintype "bidirectional"))
    )
    (net (code "87") (name "unconnected-(U$2-PadRDY-)") (class "Default")
      (node (ref "U$2") (pin "RDY-") (pinfunction "RDY-_RDY-") (pintype "bidirectional"))
    )
    (net (code "88") (name "unconnected-(U$3-I2C-3-SCL-PadI2C-3-SC)") (class "Default")
      (node (ref "U$3") (pin "I2C-3-SC") (pinfunction "I2C-3-SCL_I2C-3-SC") (pintype "bidirectional"))
    )
    (net (code "89") (name "unconnected-(U$3-PadI2C-3-12V)") (class "Default")
      (node (ref "U$3") (pin "I2C-3-12V") (pinfunction "I2C-3-12V_I2C-3-12V") (pintype "bidirectional"))
    )
    (net (code "90") (name "unconnected-(U$3-PadI2C-3-GND)") (class "Default")
      (node (ref "U$3") (pin "I2C-3-GND") (pinfunction "I2C-3-GND_I2C-3-GND") (pintype "bidirectional"))
    )
    (net (code "91") (name "unconnected-(U$3-PadI2C-3-SDA)") (class "Default")
      (node (ref "U$3") (pin "I2C-3-SDA") (pinfunction "I2C-3-SDA_I2C-3-SDA") (pintype "bidirectional"))
    )
    (net (code "92") (name "unconnected-(U$3-PadI2C-4-12V)") (class "Default")
      (node (ref "U$3") (pin "I2C-4-12V") (pinfunction "I2C-4-12V_I2C-4-12V") (pintype "bidirectional"))
    )
    (net (code "93") (name "unconnected-(U$3-PadI2C-4-GND)") (class "Default")
      (node (ref "U$3") (pin "I2C-4-GND") (pinfunction "I2C-4-GND_I2C-4-GND") (pintype "bidirectional"))
    )
    (net (code "94") (name "unconnected-(U$3-PadI2C-4-SCL)") (class "Default")
      (node (ref "U$3") (pin "I2C-4-SCL") (pinfunction "I2C-4-SCL_I2C-4-SCL") (pintype "bidirectional"))
    )
    (net (code "95") (name "unconnected-(U$3-PadI2C-4-SDA)") (class "Default")
      (node (ref "U$3") (pin "I2C-4-SDA") (pinfunction "I2C-4-SDA_I2C-4-SDA") (pintype "bidirectional"))
    )
  )
)
